# Stepper_control.net
KiCad netlist of a schematic drawn in Altium Designer
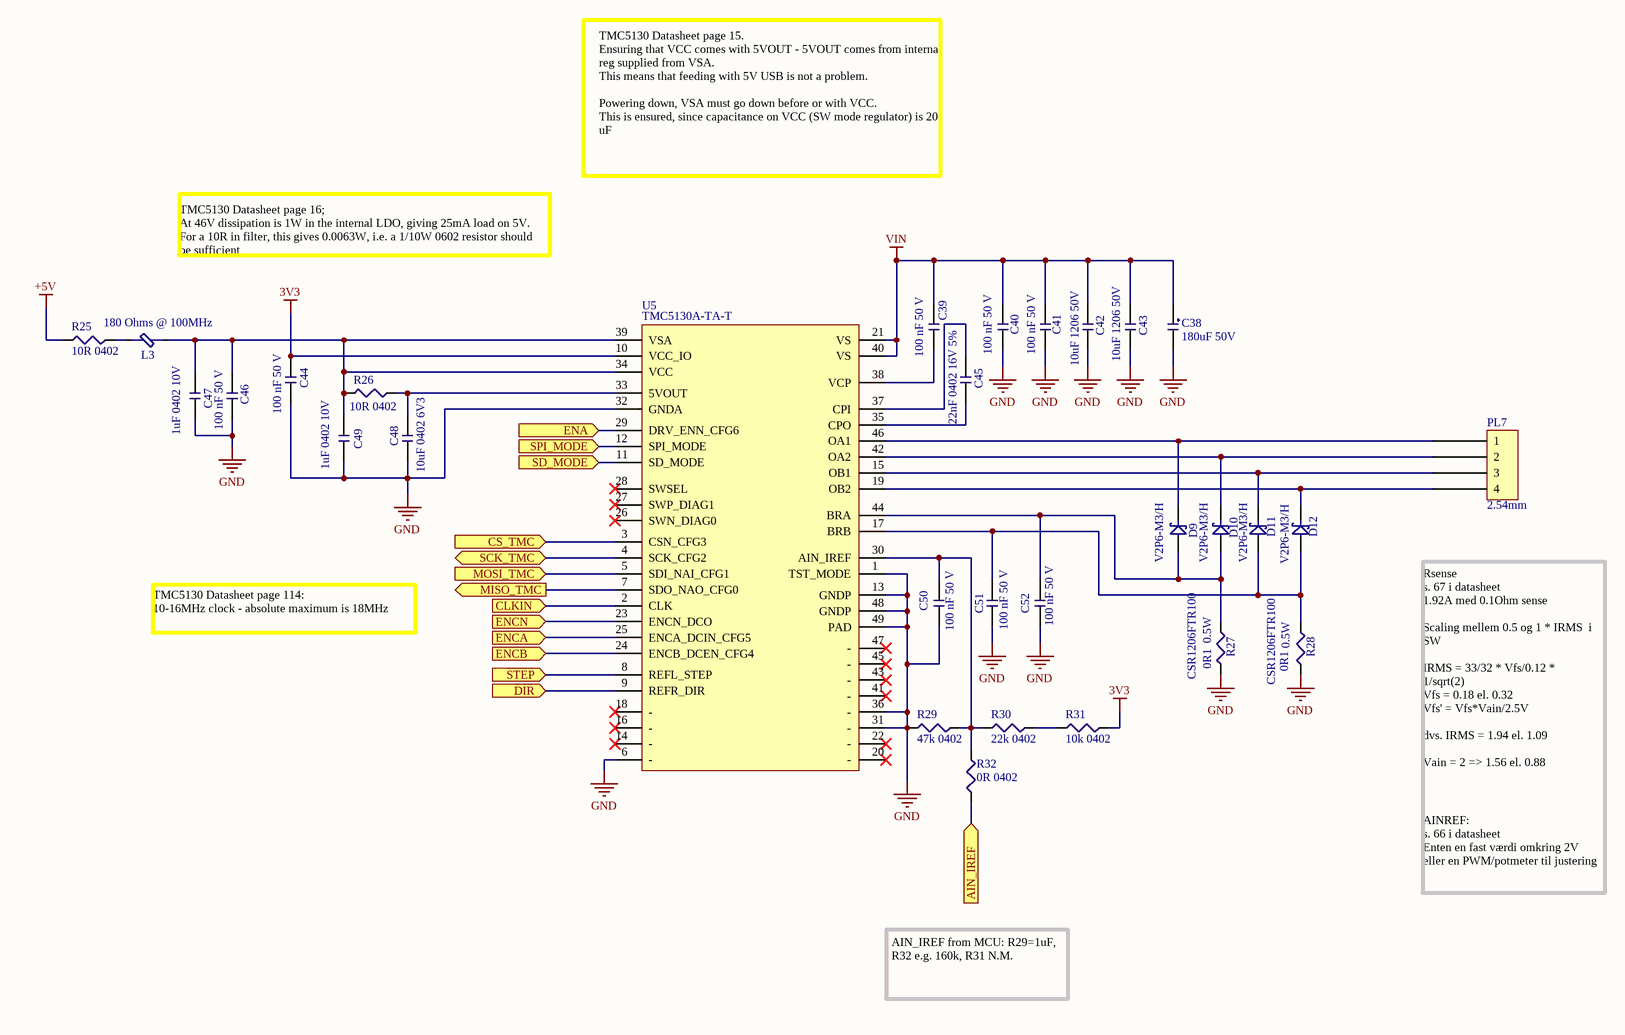
[diagram p0: Stepper_control.SchDoc]

(export (version "E")
  (design (tool "Eeschema 10.0.6"))
  (components
    (comp (ref "C38")
      (value "180uF 50V")
      (footprint "Capacitor 8x22")
      (description "180UF 20% 50V 105DEG RADIAL")
      (fields (field (name "TOLERANCE") "20%"))
      (libsource (lib "ON Development Vault") (part "Polar capacitor"))
    )
    (comp (ref "C39")
      (value "100 nF 50 V")
      (footprint "CAP_0402")
      (description "Multilayer Ceramic Capacitors MLCC - SMD/SMT .1uF 50Volts X7R +/-10% 0402 STD")
      (fields (field (name "TOLERANCE") "10%") (field (name "VOLTAGE") "50 V"))
      (libsource (lib "ON Development Vault") (part "Capacitor"))
    )
    (comp (ref "C40")
      (value "100 nF 50 V")
      (footprint "CAP_0402")
      (description "Multilayer Ceramic Capacitors MLCC - SMD/SMT .1uF 50Volts X7R +/-10% 0402 STD")
      (fields (field (name "TOLERANCE") "10%") (field (name "VOLTAGE") "50 V"))
      (libsource (lib "ON Development Vault") (part "Capacitor"))
    )
    (comp (ref "C41")
      (value "100 nF 50 V")
      (footprint "CAP_0402")
      (description "Multilayer Ceramic Capacitors MLCC - SMD/SMT .1uF 50Volts X7R +/-10% 0402 STD")
      (fields (field (name "TOLERANCE") "10%") (field (name "VOLTAGE") "50 V"))
      (libsource (lib "ON Development Vault") (part "Capacitor"))
    )
    (comp (ref "C42")
      (value "10uF 1206 50V")
      (footprint "CAP_1206")
      (description "10uF 1206 50V X5R 20%")
      (fields (field (name "TOLERANCE") "+/- 20%") (field (name "VOLTAGE") "50 V"))
      (libsource (lib "ON Development Vault") (part "Capacitor"))
    )
    (comp (ref "C43")
      (value "10uF 1206 50V")
      (footprint "CAP_1206")
      (description "10uF 1206 50V X5R 20%")
      (fields (field (name "TOLERANCE") "+/- 20%") (field (name "VOLTAGE") "50 V"))
      (libsource (lib "ON Development Vault") (part "Capacitor"))
    )
    (comp (ref "C44")
      (value "100 nF 50 V")
      (footprint "CAP_0402")
      (description "Multilayer Ceramic Capacitors MLCC - SMD/SMT .1uF 50Volts X7R +/-10% 0402 STD")
      (fields (field (name "TOLERANCE") "10%") (field (name "VOLTAGE") "50 V"))
      (libsource (lib "ON Development Vault") (part "Capacitor"))
    )
    (comp (ref "C45")
      (value "22nF 0402 16V 5%")
      (footprint "CAP_0402")
      (description "22nF 0402 16V X7R 5%")
      (fields (field (name "TOLERANCE") "5%") (field (name "VOLTAGE") "16V"))
      (libsource (lib "ON Development Vault") (part "Capacitor"))
    )
    (comp (ref "C46")
      (value "100 nF 50 V")
      (footprint "CAP_0402")
      (description "Multilayer Ceramic Capacitors MLCC - SMD/SMT .1uF 50Volts X7R +/-10% 0402 STD")
      (fields (field (name "TOLERANCE") "10%") (field (name "VOLTAGE") "50 V"))
      (libsource (lib "ON Development Vault") (part "Capacitor"))
    )
    (comp (ref "C47")
      (value "1uF 0402 10V")
      (footprint "CAP_0402")
      (description "1uF 0402 10V 10% X5R")
      (fields (field (name "TOLERANCE") "10%") (field (name "VOLTAGE") "10 V"))
      (libsource (lib "ON Development Vault") (part "Capacitor"))
    )
    (comp (ref "C48")
      (value "10uF 0402 6V3")
      (footprint "CAP_0402")
      (description "10uF 20% 0402 6V3 X6S")
      (fields (field (name "TOLERANCE") "20%") (field (name "VOLTAGE") "6V3"))
      (libsource (lib "ON Development Vault") (part "Capacitor"))
    )
    (comp (ref "C49")
      (value "1uF 0402 10V")
      (footprint "CAP_0402")
      (description "1uF 0402 10V 10% X5R")
      (fields (field (name "TOLERANCE") "10%") (field (name "VOLTAGE") "10 V"))
      (libsource (lib "ON Development Vault") (part "Capacitor"))
    )
    (comp (ref "C50")
      (value "100 nF 50 V")
      (footprint "CAP_0402")
      (description "Multilayer Ceramic Capacitors MLCC - SMD/SMT .1uF 50Volts X7R +/-10% 0402 STD")
      (fields (field (name "TOLERANCE") "10%") (field (name "VOLTAGE") "50 V"))
      (libsource (lib "ON Development Vault") (part "Capacitor"))
    )
    (comp (ref "C51")
      (value "100 nF 50 V")
      (footprint "CAP_0402")
      (description "Multilayer Ceramic Capacitors MLCC - SMD/SMT .1uF 50Volts X7R +/-10% 0402 STD")
      (fields (field (name "TOLERANCE") "10%") (field (name "VOLTAGE") "50 V"))
      (libsource (lib "ON Development Vault") (part "Capacitor"))
    )
    (comp (ref "C52")
      (value "100 nF 50 V")
      (footprint "CAP_0402")
      (description "Multilayer Ceramic Capacitors MLCC - SMD/SMT .1uF 50Volts X7R +/-10% 0402 STD")
      (fields (field (name "TOLERANCE") "10%") (field (name "VOLTAGE") "50 V"))
      (libsource (lib "ON Development Vault") (part "Capacitor"))
    )
    (comp (ref "D9")
      (value "V2P6-M3/H")
      (footprint "MicroSMP")
      (description "DIODE SCHOTTKY 60V 2A MICROSMP")
      (libsource (lib "ON Development Vault") (part "Schottky"))
    )
    (comp (ref "D10")
      (value "V2P6-M3/H")
      (footprint "MicroSMP")
      (description "DIODE SCHOTTKY 60V 2A MICROSMP")
      (libsource (lib "ON Development Vault") (part "Schottky"))
    )
    (comp (ref "D11")
      (value "V2P6-M3/H")
      (footprint "MicroSMP")
      (description "DIODE SCHOTTKY 60V 2A MICROSMP")
      (libsource (lib "ON Development Vault") (part "Schottky"))
    )
    (comp (ref "D12")
      (value "V2P6-M3/H")
      (footprint "MicroSMP")
      (description "DIODE SCHOTTKY 60V 2A MICROSMP")
      (libsource (lib "ON Development Vault") (part "Schottky"))
    )
    (comp (ref "L3")
      (value "180 Ohms @ 100MHz")
      (footprint "IND_0603")
      (description "FERRITE BEAD 180 OHM 0603 1LN")
      (fields (field (name "MFG. PART NUMBER") "BLM18PG181SN1D"))
      (libsource (lib "ON Development Vault") (part "Ferrite"))
    )
    (comp (ref "PL7")
      (value "2.54mm")
      (footprint "4-pin 2.54mm header")
      (description "Pin header 4-pin 2.54mm male")
      (fields (field (name "MFG. PART NUMBER") "DS1021-1*4SF1-1"))
      (libsource (lib "ON Development Vault") (part "4-pin header"))
    )
    (comp (ref "R25")
      (value "10R 0402")
      (footprint "RES_0402")
      (description "RES SMD 10 OHM 1% 1/16W 0402")
      (fields (field (name "POWER") "63mW") (field (name "TOLERANCE") "1%"))
      (libsource (lib "ON Development Vault") (part "Resistor"))
    )
    (comp (ref "R26")
      (value "10R 0402")
      (footprint "RES_0402")
      (description "RES SMD 10 OHM 1% 1/16W 0402")
      (fields (field (name "POWER") "63mW") (field (name "TOLERANCE") "1%"))
      (libsource (lib "ON Development Vault") (part "Resistor"))
    )
    (comp (ref "R27")
      (value "CSR1206FTR100")
      (footprint "RES_1206")
      (description "RES 0.1 OHM 1% 1/2W 1206")
      (fields
        (field (name "POWER") "0.5W")
        (field (name "TOLERANCE") "1%")
        (field (name "ALTIUM_VALUE") "0R1")
      )
      (libsource (lib "ON Development Vault") (part "Resistor"))
    )
    (comp (ref "R28")
      (value "CSR1206FTR100")
      (footprint "RES_1206")
      (description "RES 0.1 OHM 1% 1/2W 1206")
      (fields
        (field (name "POWER") "0.5W")
        (field (name "TOLERANCE") "1%")
        (field (name "ALTIUM_VALUE") "0R1")
      )
      (libsource (lib "ON Development Vault") (part "Resistor"))
    )
    (comp (ref "R29")
      (value "47k 0402")
      (footprint "RES_0402")
      (description "RES SMD 47K OHM 1% 1/16W 0402")
      (fields (field (name "POWER") "1/16W") (field (name "TOLERANCE") "1%"))
      (libsource (lib "ON Development Vault") (part "Resistor"))
    )
    (comp (ref "R30")
      (value "22k 0402")
      (footprint "RES_0402")
      (description "RES SMD 22K OHM 1% 1/16W 0402")
      (fields (field (name "POWER") "1/16W") (field (name "TOLERANCE") "1%"))
      (libsource (lib "ON Development Vault") (part "Resistor"))
    )
    (comp (ref "R31")
      (value "10k 0402")
      (footprint "RES_0402")
      (description "RES SMD 10K OHM 1% 1/16W 0402")
      (fields (field (name "POWER") "1/16 W") (field (name "TOLERANCE") "1 %"))
      (libsource (lib "ON Development Vault") (part "Resistor"))
    )
    (comp (ref "R32")
      (value "0R 0402")
      (footprint "RES_0402")
      (description "RES SMD 0 OHM 1/16W 0402")
      (fields (field (name "POWER") "63mW") (field (name "MFG. PART NUMBER") "RC0402JR-070RL"))
      (libsource (lib "ON Development Vault") (part "Resistor"))
    )
    (comp (ref "U5")
      (value "TMC5130A-TA-T")
      (footprint "TSQFP50P900X900X120_HS-49N")
      (description "IC MOTOR CTLR/DVR SPI 48QFP")
      (libsource (lib "ON Development Vault") (part "TMC5130A-TA"))
    )
  )
  (nets
    (net (code "1") (name "+5V") (class "Default")
      (node (ref "R25") (pin "2") (pinfunction "2_2") (pintype "passive"))
    )
    (net (code "2") (name "/AIN_IREF") (class "Default")
      (node (ref "R32") (pin "1") (pinfunction "1_1") (pintype "passive"))
    )
    (net (code "3") (name "/CLKIN") (class "Default")
      (node (ref "U5") (pin "2") (pinfunction "CLK_2") (pintype "passive"))
    )
    (net (code "4") (name "/CS_TMC") (class "Default")
      (node (ref "U5") (pin "3") (pinfunction "CSN_CFG3_3") (pintype "passive"))
    )
    (net (code "5") (name "/DIR") (class "Default")
      (node (ref "U5") (pin "9") (pinfunction "REFR_DIR_9") (pintype "passive"))
    )
    (net (code "6") (name "/ENA") (class "Default")
      (node (ref "U5") (pin "29") (pinfunction "DRV_ENN_CFG6_29") (pintype "passive"))
    )
    (net (code "7") (name "/ENCA") (class "Default")
      (node (ref "U5") (pin "25") (pinfunction "ENCA_DCIN_CFG5_25") (pintype "passive"))
    )
    (net (code "8") (name "/ENCB") (class "Default")
      (node (ref "U5") (pin "24") (pinfunction "ENCB_DCEN_CFG4_24") (pintype "passive"))
    )
    (net (code "9") (name "/ENCN") (class "Default")
      (node (ref "U5") (pin "23") (pinfunction "ENCN_DCO_23") (pintype "passive"))
    )
    (net (code "10") (name "/MISO_TMC") (class "Default")
      (node (ref "U5") (pin "7") (pinfunction "SDO_NAO_CFG0_7") (pintype "passive"))
    )
    (net (code "11") (name "/MOSI_TMC") (class "Default")
      (node (ref "U5") (pin "5") (pinfunction "SDI_NAI_CFG1_5") (pintype "passive"))
    )
    (net (code "12") (name "/SCK_TMC") (class "Default")
      (node (ref "U5") (pin "4") (pinfunction "SCK_CFG2_4") (pintype "passive"))
    )
    (net (code "13") (name "/SD_MODE") (class "Default")
      (node (ref "U5") (pin "11") (pinfunction "SD_MODE_11") (pintype "passive"))
    )
    (net (code "14") (name "/SPI_MODE") (class "Default")
      (node (ref "U5") (pin "12") (pinfunction "SPI_MODE_12") (pintype "passive"))
    )
    (net (code "15") (name "/STEP") (class "Default")
      (node (ref "U5") (pin "8") (pinfunction "REFL_STEP_8") (pintype "passive"))
    )
    (net (code "16") (name "3V3") (class "Default")
      (node (ref "C44") (pin "1") (pinfunction "1_1") (pintype "passive"))
      (node (ref "R31") (pin "1") (pinfunction "1_1") (pintype "passive"))
      (node (ref "U5") (pin "10") (pinfunction "VCC_IO_10") (pintype "passive"))
    )
    (net (code "17") (name "GND") (class "Default")
      (node (ref "C38") (pin "2") (pinfunction "2_2") (pintype "passive"))
      (node (ref "C40") (pin "2") (pinfunction "2_2") (pintype "passive"))
      (node (ref "C41") (pin "2") (pinfunction "2_2") (pintype "passive"))
      (node (ref "C42") (pin "2") (pinfunction "2_2") (pintype "passive"))
      (node (ref "C43") (pin "2") (pinfunction "2_2") (pintype "passive"))
      (node (ref "C44") (pin "2") (pinfunction "2_2") (pintype "passive"))
      (node (ref "C46") (pin "2") (pinfunction "2_2") (pintype "passive"))
      (node (ref "C47") (pin "1") (pinfunction "1_1") (pintype "passive"))
      (node (ref "C48") (pin "1") (pinfunction "1_1") (pintype "passive"))
      (node (ref "C49") (pin "1") (pinfunction "1_1") (pintype "passive"))
      (node (ref "C50") (pin "2") (pinfunction "2_2") (pintype "passive"))
      (node (ref "C51") (pin "2") (pinfunction "2_2") (pintype "passive"))
      (node (ref "C52") (pin "2") (pinfunction "2_2") (pintype "passive"))
      (node (ref "R27") (pin "1") (pinfunction "1_1") (pintype "passive"))
      (node (ref "R28") (pin "1") (pinfunction "1_1") (pintype "passive"))
      (node (ref "R29") (pin "2") (pinfunction "2_2") (pintype "passive"))
      (node (ref "U5") (pin "1") (pinfunction "TST_MODE_1") (pintype "passive"))
      (node (ref "U5") (pin "13") (pinfunction "GNDP_13") (pintype "passive"))
      (node (ref "U5") (pin "31") (pinfunction "-_31") (pintype "passive"))
      (node (ref "U5") (pin "32") (pinfunction "GNDA_32") (pintype "passive"))
      (node (ref "U5") (pin "36") (pinfunction "-_36") (pintype "passive"))
      (node (ref "U5") (pin "48") (pinfunction "GNDP_48") (pintype "passive"))
      (node (ref "U5") (pin "49") (pinfunction "PAD_49") (pintype "passive"))
      (node (ref "U5") (pin "6") (pinfunction "-_6") (pintype "passive"))
    )
    (net (code "18") (name "Net-(L3-Pad1)") (class "Default")
      (node (ref "L3") (pin "1") (pinfunction "1_1") (pintype "passive"))
      (node (ref "R25") (pin "1") (pinfunction "1_1") (pintype "passive"))
    )
    (net (code "19") (name "Net-(R30-Pad2)") (class "Default")
      (node (ref "R30") (pin "2") (pinfunction "2_2") (pintype "passive"))
      (node (ref "R31") (pin "2") (pinfunction "2_2") (pintype "passive"))
    )
    (net (code "20") (name "Net-(U5-5VOUT)") (class "Default")
      (node (ref "C48") (pin "2") (pinfunction "2_2") (pintype "passive"))
      (node (ref "R26") (pin "2") (pinfunction "2_2") (pintype "passive"))
      (node (ref "U5") (pin "33") (pinfunction "5VOUT_33") (pintype "passive"))
    )
    (net (code "21") (name "Net-(U5-AIN_IREF)") (class "Default")
      (node (ref "C50") (pin "1") (pinfunction "1_1") (pintype "passive"))
      (node (ref "R29") (pin "1") (pinfunction "1_1") (pintype "passive"))
      (node (ref "R30") (pin "1") (pinfunction "1_1") (pintype "passive"))
      (node (ref "R32") (pin "2") (pinfunction "2_2") (pintype "passive"))
      (node (ref "U5") (pin "30") (pinfunction "AIN_IREF_30") (pintype "passive"))
    )
    (net (code "22") (name "Net-(U5-BRA)") (class "Default")
      (node (ref "C52") (pin "1") (pinfunction "1_1") (pintype "passive"))
      (node (ref "D10") (pin "1") (pinfunction "1_1") (pintype "passive"))
      (node (ref "D9") (pin "1") (pinfunction "1_1") (pintype "passive"))
      (node (ref "R27") (pin "2") (pinfunction "2_2") (pintype "passive"))
      (node (ref "U5") (pin "44") (pinfunction "BRA_44") (pintype "passive"))
    )
    (net (code "23") (name "Net-(U5-BRB)") (class "Default")
      (node (ref "C51") (pin "1") (pinfunction "1_1") (pintype "passive"))
      (node (ref "D11") (pin "1") (pinfunction "1_1") (pintype "passive"))
      (node (ref "D12") (pin "1") (pinfunction "1_1") (pintype "passive"))
      (node (ref "R28") (pin "2") (pinfunction "2_2") (pintype "passive"))
      (node (ref "U5") (pin "17") (pinfunction "BRB_17") (pintype "passive"))
    )
    (net (code "24") (name "Net-(U5-CPI)") (class "Default")
      (node (ref "C45") (pin "2") (pinfunction "2_2") (pintype "passive"))
      (node (ref "U5") (pin "37") (pinfunction "CPI_37") (pintype "passive"))
    )
    (net (code "25") (name "Net-(U5-CPO)") (class "Default")
      (node (ref "C45") (pin "1") (pinfunction "1_1") (pintype "passive"))
      (node (ref "U5") (pin "35") (pinfunction "CPO_35") (pintype "passive"))
    )
    (net (code "26") (name "Net-(U5-OA1)") (class "Default")
      (node (ref "D9") (pin "2") (pinfunction "2_2") (pintype "passive"))
      (node (ref "PL7") (pin "1") (pinfunction "1_1") (pintype "passive"))
      (node (ref "U5") (pin "46") (pinfunction "OA1_46") (pintype "passive"))
    )
    (net (code "27") (name "Net-(U5-OA2)") (class "Default")
      (node (ref "D10") (pin "2") (pinfunction "2_2") (pintype "passive"))
      (node (ref "PL7") (pin "2") (pinfunction "2_2") (pintype "passive"))
      (node (ref "U5") (pin "42") (pinfunction "OA2_42") (pintype "passive"))
    )
    (net (code "28") (name "Net-(U5-OB1)") (class "Default")
      (node (ref "D11") (pin "2") (pinfunction "2_2") (pintype "passive"))
      (node (ref "PL7") (pin "3") (pinfunction "3_3") (pintype "passive"))
      (node (ref "U5") (pin "15") (pinfunction "OB1_15") (pintype "passive"))
    )
    (net (code "29") (name "Net-(U5-OB2)") (class "Default")
      (node (ref "D12") (pin "2") (pinfunction "2_2") (pintype "passive"))
      (node (ref "PL7") (pin "4") (pinfunction "4_4") (pintype "passive"))
      (node (ref "U5") (pin "19") (pinfunction "OB2_19") (pintype "passive"))
    )
    (net (code "30") (name "Net-(U5-VCC)") (class "Default")
      (node (ref "C46") (pin "1") (pinfunction "1_1") (pintype "passive"))
      (node (ref "C47") (pin "2") (pinfunction "2_2") (pintype "passive"))
      (node (ref "C49") (pin "2") (pinfunction "2_2") (pintype "passive"))
      (node (ref "L3") (pin "2") (pinfunction "2_2") (pintype "passive"))
      (node (ref "R26") (pin "1") (pinfunction "1_1") (pintype "passive"))
      (node (ref "U5") (pin "34") (pinfunction "VCC_34") (pintype "passive"))
      (node (ref "U5") (pin "39") (pinfunction "VSA_39") (pintype "passive"))
    )
    (net (code "31") (name "Net-(U5-VCP)") (class "Default")
      (node (ref "C39") (pin "1") (pinfunction "1_1") (pintype "passive"))
      (node (ref "U5") (pin "38") (pinfunction "VCP_38") (pintype "passive"))
    )
    (net (code "32") (name "VIN") (class "Default")
      (node (ref "C38") (pin "1") (pinfunction "1_1") (pintype "passive"))
      (node (ref "C39") (pin "2") (pinfunction "2_2") (pintype "passive"))
      (node (ref "C40") (pin "1") (pinfunction "1_1") (pintype "passive"))
      (node (ref "C41") (pin "1") (pinfunction "1_1") (pintype "passive"))
      (node (ref "C42") (pin "1") (pinfunction "1_1") (pintype "passive"))
      (node (ref "C43") (pin "1") (pinfunction "1_1") (pintype "passive"))
      (node (ref "U5") (pin "21") (pinfunction "VS_21") (pintype "passive"))
      (node (ref "U5") (pin "40") (pinfunction "VS_40") (pintype "passive"))
    )
    (net (code "33") (name "unconnected-(U5---Pad14)") (class "Default")
      (node (ref "U5") (pin "14") (pinfunction "-_14") (pintype "passive+no_connect"))
    )
    (net (code "34") (name "unconnected-(U5---Pad16)") (class "Default")
      (node (ref "U5") (pin "16") (pinfunction "-_16") (pintype "passive+no_connect"))
    )
    (net (code "35") (name "unconnected-(U5---Pad18)") (class "Default")
      (node (ref "U5") (pin "18") (pinfunction "-_18") (pintype "passive+no_connect"))
    )
    (net (code "36") (name "unconnected-(U5---Pad20)") (class "Default")
      (node (ref "U5") (pin "20") (pinfunction "-_20") (pintype "passive+no_connect"))
    )
    (net (code "37") (name "unconnected-(U5---Pad22)") (class "Default")
      (node (ref "U5") (pin "22") (pinfunction "-_22") (pintype "passive+no_connect"))
    )
    (net (code "38") (name "unconnected-(U5---Pad41)") (class "Default")
      (node (ref "U5") (pin "41") (pinfunction "-_41") (pintype "passive+no_connect"))
    )
    (net (code "39") (name "unconnected-(U5---Pad43)") (class "Default")
      (node (ref "U5") (pin "43") (pinfunction "-_43") (pintype "passive+no_connect"))
    )
    (net (code "40") (name "unconnected-(U5---Pad45)") (class "Default")
      (node (ref "U5") (pin "45") (pinfunction "-_45") (pintype "passive+no_connect"))
    )
    (net (code "41") (name "unconnected-(U5---Pad47)") (class "Default")
      (node (ref "U5") (pin "47") (pinfunction "-_47") (pintype "passive+no_connect"))
    )
    (net (code "42") (name "unconnected-(U5-SWN_DIAG0-Pad26)") (class "Default")
      (node (ref "U5") (pin "26") (pinfunction "SWN_DIAG0_26") (pintype "passive+no_connect"))
    )
    (net (code "43") (name "unconnected-(U5-SWP_DIAG1-Pad27)") (class "Default")
      (node (ref "U5") (pin "27") (pinfunction "SWP_DIAG1_27") (pintype "passive+no_connect"))
    )
    (net (code "44") (name "unconnected-(U5-SWSEL-Pad28)") (class "Default")
      (node (ref "U5") (pin "28") (pinfunction "SWSEL_28") (pintype "passive+no_connect"))
    )
  )
)
